# PULSE_SELECT.net
KiCad netlist of a schematic drawn in Altium Designer
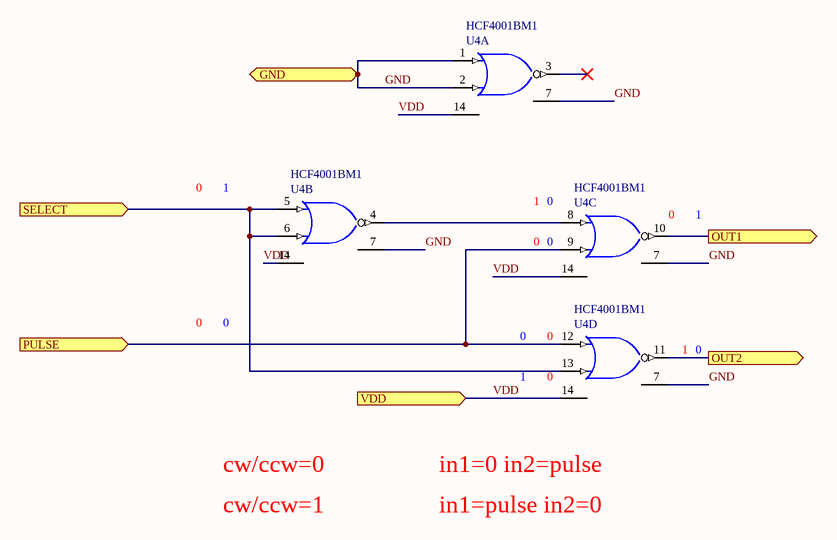
[diagram p0: PULSE_SELECT.SchDoc]

(export (version "E")
  (design (tool "Eeschema 10.0.6"))
  (components
    (comp (ref "U4")
      (value "HCF4001BM1")
      (footprint "SO14_N")
      (description "Quad 2-Input NOR Gate")
      (fields (field (name "PUBLISHER") "Altium Limited"))
      (libsource (lib "ST Logic Gate") (part "HCF4001BM1"))
    )
  )
  (nets
    (net (code "1") (name "/GND") (class "Default")
      (node (ref "U4") (pin "1") (pinfunction "A_1") (pintype "input"))
      (node (ref "U4") (pin "2") (pinfunction "B_2") (pintype "input"))
      (node (ref "U4") (pin "7") (pinfunction "GND_7") (pintype "passive"))
    )
    (net (code "2") (name "/OUT1") (class "Default")
      (node (ref "U4") (pin "10") (pinfunction "L_10") (pintype "output"))
    )
    (net (code "3") (name "/OUT2") (class "Default")
      (node (ref "U4") (pin "11") (pinfunction "M_11") (pintype "output"))
    )
    (net (code "4") (name "/PULSE") (class "Default")
      (node (ref "U4") (pin "12") (pinfunction "G_12") (pintype "input"))
      (node (ref "U4") (pin "9") (pinfunction "F_9") (pintype "input"))
    )
    (net (code "5") (name "/SELECT") (class "Default")
      (node (ref "U4") (pin "13") (pinfunction "H_13") (pintype "input"))
      (node (ref "U4") (pin "5") (pinfunction "C_5") (pintype "input"))
      (node (ref "U4") (pin "6") (pinfunction "D_6") (pintype "input"))
    )
    (net (code "6") (name "/VDD") (class "Default")
      (node (ref "U4") (pin "14") (pinfunction "VDD_14") (pintype "passive"))
    )
    (net (code "7") (name "Net-(U4B-K)") (class "Default")
      (node (ref "U4") (pin "4") (pinfunction "K_4") (pintype "output"))
      (node (ref "U4") (pin "8") (pinfunction "E_8") (pintype "input"))
    )
    (net (code "8") (name "unconnected-(U4A-J-Pad3)") (class "Default")
      (node (ref "U4") (pin "3") (pinfunction "J_3") (pintype "output+no_connect"))
    )
  )
)
